# Adafruit_Rotary_Trinkey.net
KiCad netlist of a schematic drawn in EAGLE
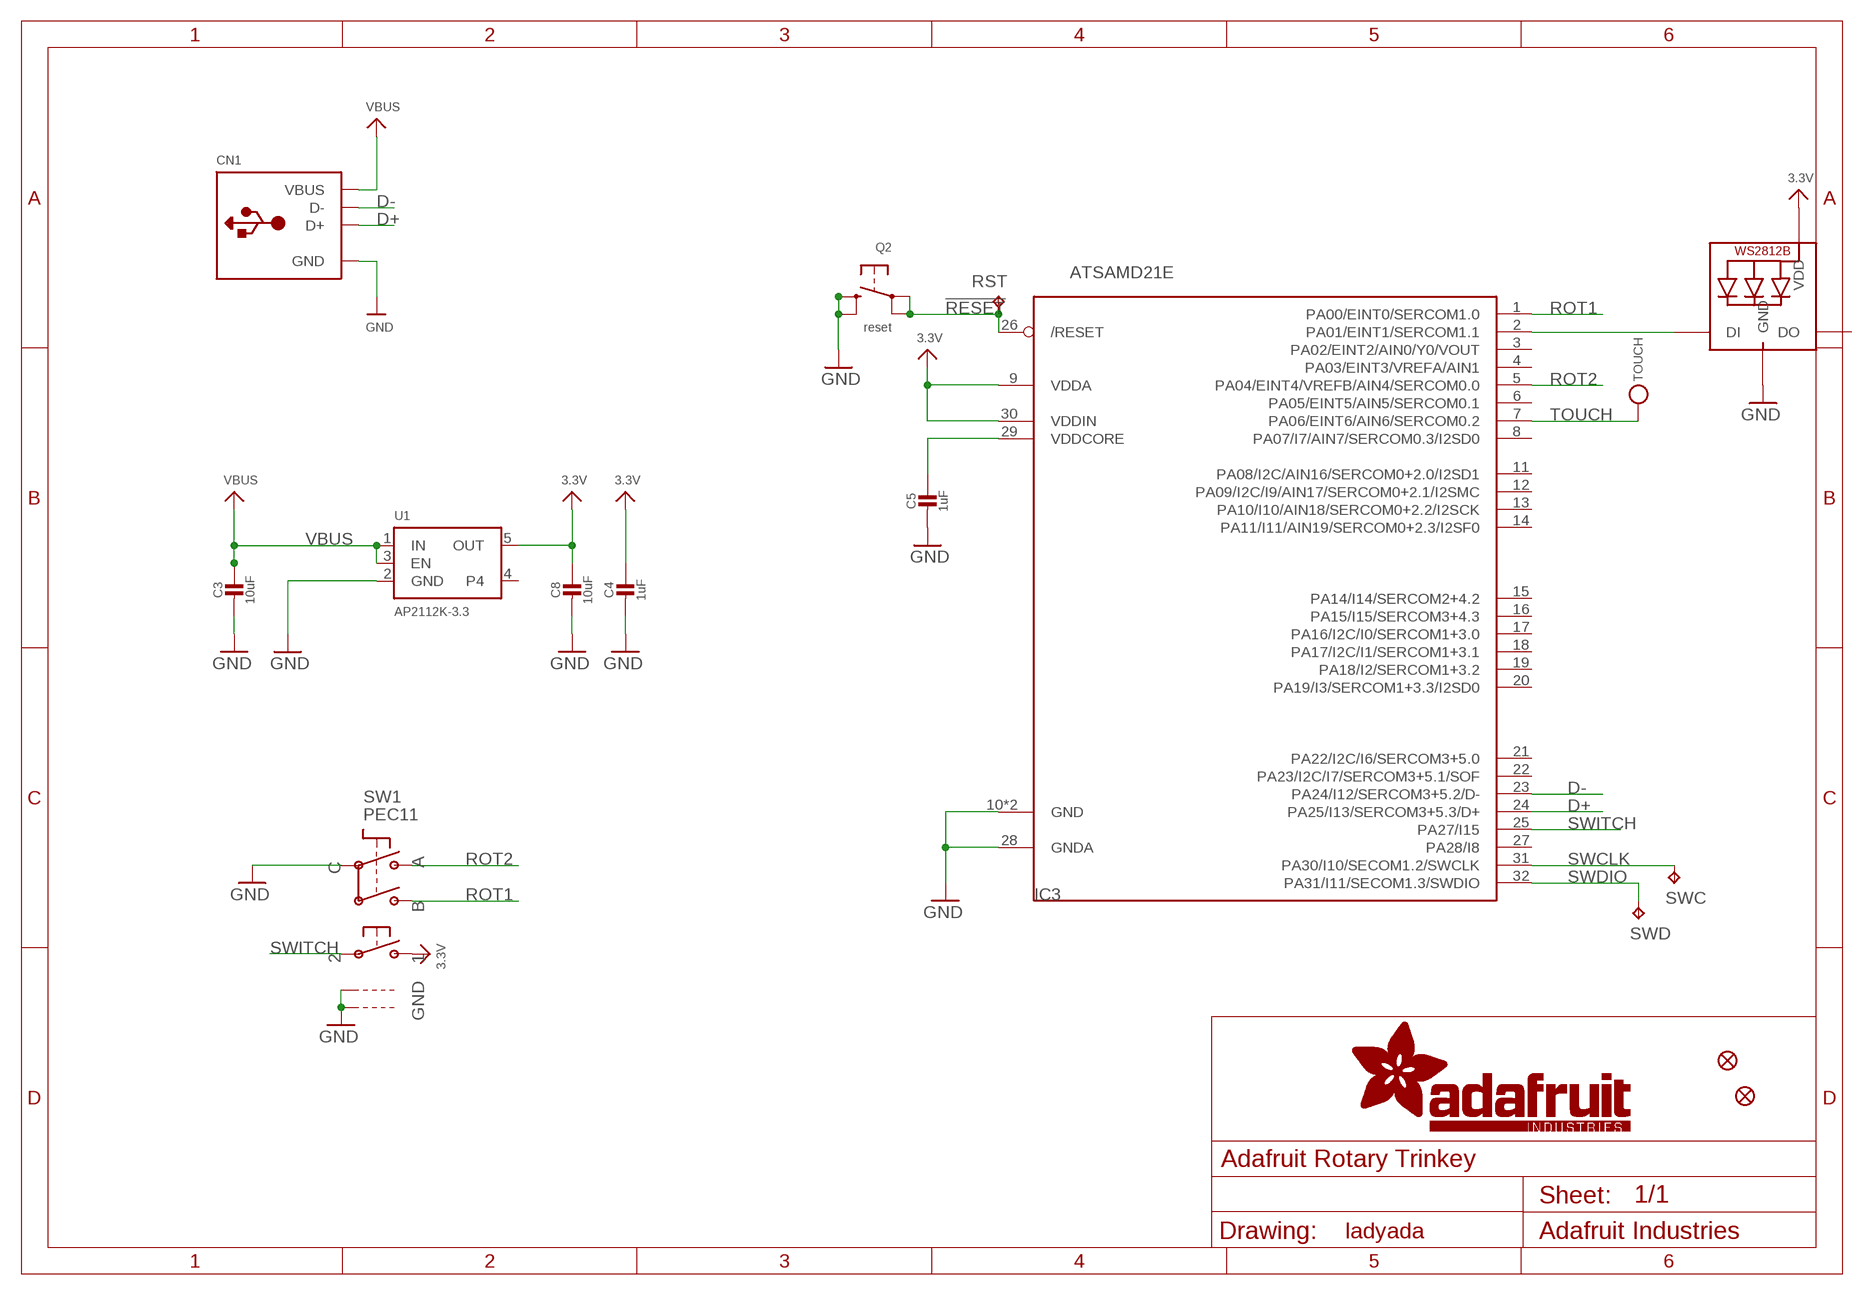
[diagram p0: schematic, sheet 1]

(export (version "E")
  (design (tool "Eeschema 10.0.6"))
  (components
    (comp (ref "C3")
      (value "10uF")
      (footprint "eagle-import:0805-NO")
      (libsource (lib "eagle-import") (part "CAP_CERAMIC0805-NOOUTLINE"))
    )
    (comp (ref "C4")
      (value "1uF")
      (footprint "eagle-import:0603-NO")
      (libsource (lib "eagle-import") (part "CAP_CERAMIC0603_NO"))
    )
    (comp (ref "C5")
      (value "1uF")
      (footprint "eagle-import:0603-NO")
      (libsource (lib "eagle-import") (part "CAP_CERAMIC0603_NO"))
    )
    (comp (ref "C8")
      (value "10uF")
      (footprint "eagle-import:0805-NO")
      (libsource (lib "eagle-import") (part "CAP_CERAMIC0805-NOOUTLINE"))
    )
    (comp (ref "CN1")
      (value "USB_TYPEAPCB")
      (footprint "eagle-import:USBA_PCB")
      (libsource (lib "eagle-import") (part "USB_TYPEAPCB"))
    )
    (comp (ref "FID1")
      (value "FIDUCIAL_1MM")
      (footprint "eagle-import:FIDUCIAL_1MM")
      (libsource (lib "eagle-import") (part "FIDUCIAL_1MM"))
    )
    (comp (ref "FID2")
      (value "FIDUCIAL_1MM")
      (footprint "eagle-import:FIDUCIAL_1MM")
      (libsource (lib "eagle-import") (part "FIDUCIAL_1MM"))
    )
    (comp (ref "IC3")
      (value "ATSAMD21E")
      (footprint "eagle-import:QFN32_5MM")
      (libsource (lib "eagle-import") (part "ATSAMD21E"))
    )
    (comp (ref "LED1")
      (value "WS2812B_SK6805_1515")
      (footprint "eagle-import:SK6805_1515")
      (libsource (lib "eagle-import") (part "WS2812B_SK6805_1515"))
    )
    (comp (ref "Q2")
      (value "reset")
      (footprint "eagle-import:BTN_KMR2_4.6X2.8")
      (libsource (lib "eagle-import") (part "SWITCH_TACT_SMT4.6X2.8"))
    )
    (comp (ref "RST")
      (value "TPTP16R")
      (footprint "eagle-import:TP16R")
      (libsource (lib "eagle-import") (part "TPTP16R"))
    )
    (comp (ref "SW1")
      (value "PEC11")
      (footprint "eagle-import:PEC11+SWITCH")
      (libsource (lib "eagle-import") (part "ENCODER_PLUS_SWITCH_PEC11_BOURNS"))
    )
    (comp (ref "SWC")
      (value "TPTP16R")
      (footprint "eagle-import:TP16R")
      (libsource (lib "eagle-import") (part "TPTP16R"))
    )
    (comp (ref "SWD")
      (value "TPTP16R")
      (footprint "eagle-import:TP16R")
      (libsource (lib "eagle-import") (part "TPTP16R"))
    )
    (comp (ref "TOUCH")
      (value "TESTPOINTPAD1MM")
      (footprint "eagle-import:TESTPOINT_PAD_1MM")
      (libsource (lib "eagle-import") (part "TESTPOINTPAD1MM"))
    )
    (comp (ref "U1")
      (value "AP2112K-3.3")
      (footprint "eagle-import:SOT23-5")
      (libsource (lib "eagle-import") (part "VREG_SOT23-5"))
    )
  )
  (nets
    (net (code "1") (name "/D+") (class "Default")
      (node (ref "CN1") (pin "USB_PLUS") (pinfunction "D+_USB_PLUS") (pintype "bidirectional"))
      (node (ref "IC3") (pin "24") (pinfunction "PA25/I13/SERCOM3+5.3/D+_24") (pintype "bidirectional"))
    )
    (net (code "2") (name "/D-") (class "Default")
      (node (ref "CN1") (pin "USB_NEG") (pinfunction "D-_USB_NEG") (pintype "bidirectional"))
      (node (ref "IC3") (pin "23") (pinfunction "PA24/I12/SERCOM3+5.2/D-_23") (pintype "bidirectional"))
    )
    (net (code "3") (name "/ROT1") (class "Default")
      (node (ref "IC3") (pin "1") (pinfunction "PA00/EINT0/SERCOM1.0_1") (pintype "bidirectional"))
      (node (ref "SW1") (pin "P$B") (pinfunction "P$B_P$B") (pintype "passive"))
    )
    (net (code "4") (name "/ROT2") (class "Default")
      (node (ref "IC3") (pin "5") (pinfunction "PA04/EINT4/VREFB/AIN4/SERCOM0.0_5") (pintype "bidirectional"))
      (node (ref "SW1") (pin "P$A") (pinfunction "P$A_P$A") (pintype "passive"))
    )
    (net (code "5") (name "/SWCLK") (class "Default")
      (node (ref "IC3") (pin "31") (pinfunction "PA30/I10/SECOM1.2/SWCLK_31") (pintype "bidirectional"))
      (node (ref "SWC") (pin "TP") (pinfunction "TP_TP") (pintype "input"))
    )
    (net (code "6") (name "/SWDIO") (class "Default")
      (node (ref "IC3") (pin "32") (pinfunction "PA31/I11/SECOM1.3/SWDIO_32") (pintype "bidirectional"))
      (node (ref "SWD") (pin "TP") (pinfunction "TP_TP") (pintype "input"))
    )
    (net (code "7") (name "/SWITCH") (class "Default")
      (node (ref "IC3") (pin "25") (pinfunction "PA27/I15_25") (pintype "bidirectional"))
      (node (ref "SW1") (pin "P$2") (pinfunction "P$2_P$2") (pintype "passive"))
    )
    (net (code "8") (name "/TOUCH") (class "Default")
      (node (ref "IC3") (pin "7") (pinfunction "PA06/EINT6/AIN6/SERCOM0.2_7") (pintype "bidirectional"))
      (node (ref "TOUCH") (pin "P$1") (pinfunction "P$1_P$1") (pintype "bidirectional"))
    )
    (net (code "9") (name "/~{RESET}") (class "Default")
      (node (ref "IC3") (pin "26") (pinfunction "/RESET_26") (pintype "bidirectional"))
      (node (ref "Q2") (pin "A") (pinfunction "P_A") (pintype "passive"))
      (node (ref "Q2") (pin "A'") (pinfunction "P1_A'") (pintype "passive"))
      (node (ref "RST") (pin "TP") (pinfunction "TP_TP") (pintype "input"))
    )
    (net (code "10") (name "3.3V") (class "Default")
      (node (ref "C4") (pin "1") (pinfunction "1_1") (pintype "passive"))
      (node (ref "C8") (pin "1") (pinfunction "1_1") (pintype "passive"))
      (node (ref "IC3") (pin "30") (pinfunction "VDDIN_30") (pintype "power_in"))
      (node (ref "IC3") (pin "9") (pinfunction "VDDA_9") (pintype "power_in"))
      (node (ref "LED1") (pin "2") (pinfunction "VDD_2") (pintype "power_in"))
      (node (ref "SW1") (pin "P$1") (pinfunction "P$1_P$1") (pintype "passive"))
      (node (ref "U1") (pin "5") (pinfunction "OUT_5") (pintype "power_in"))
    )
    (net (code "11") (name "GND") (class "Default")
      (node (ref "C3") (pin "2") (pinfunction "2_2") (pintype "passive"))
      (node (ref "C4") (pin "2") (pinfunction "2_2") (pintype "passive"))
      (node (ref "C5") (pin "2") (pinfunction "2_2") (pintype "passive"))
      (node (ref "C8") (pin "2") (pinfunction "2_2") (pintype "passive"))
      (node (ref "CN1") (pin "GND") (pinfunction "GND_GND") (pintype "power_in"))
      (node (ref "IC3") (pin "10") (pinfunction "GND_10") (pintype "power_in"))
      (node (ref "IC3") (pin "28") (pinfunction "GNDA_28") (pintype "power_in"))
      (node (ref "IC3") (pin "33") (pinfunction "GND_33") (pintype "power_in"))
      (node (ref "LED1") (pin "4") (pinfunction "GND_4") (pintype "power_in"))
      (node (ref "Q2") (pin "B") (pinfunction "S_B") (pintype "passive"))
      (node (ref "Q2") (pin "B'") (pinfunction "S1_B'") (pintype "passive"))
      (node (ref "SW1") (pin "P$C") (pinfunction "P$C_P$C") (pintype "passive"))
      (node (ref "SW1") (pin "P$GND1") (pinfunction "P$GND1_P$GND1") (pintype "passive"))
      (node (ref "SW1") (pin "P$GND2") (pinfunction "P$GND2_P$GND2") (pintype "passive"))
      (node (ref "U1") (pin "2") (pinfunction "GND_2") (pintype "power_in"))
    )
    (net (code "12") (name "Net-(IC3-PA01{slash}EINT1{slash}SERCOM1.1)") (class "Default")
      (node (ref "IC3") (pin "2") (pinfunction "PA01/EINT1/SERCOM1.1_2") (pintype "bidirectional"))
      (node (ref "LED1") (pin "1") (pinfunction "DI_1") (pintype "input"))
    )
    (net (code "13") (name "Net-(IC3-VDDCORE)") (class "Default")
      (node (ref "C5") (pin "1") (pinfunction "1_1") (pintype "passive"))
      (node (ref "IC3") (pin "29") (pinfunction "VDDCORE_29") (pintype "power_in"))
    )
    (net (code "14") (name "VBUS") (class "Default")
      (node (ref "C3") (pin "1") (pinfunction "1_1") (pintype "passive"))
      (node (ref "CN1") (pin "VCC") (pinfunction "VBUS_VCC") (pintype "power_in"))
      (node (ref "U1") (pin "1") (pinfunction "IN_1") (pintype "power_in"))
      (node (ref "U1") (pin "3") (pinfunction "EN_3") (pintype "input"))
    )
    (net (code "15") (name "unconnected-(IC3-PA02{slash}EINT2{slash}AIN0{slash}Y0{slash}VOUT-Pad3)") (class "Default")
      (node (ref "IC3") (pin "3") (pinfunction "PA02/EINT2/AIN0/Y0/VOUT_3") (pintype "bidirectional"))
    )
    (net (code "16") (name "unconnected-(IC3-PA03{slash}EINT3{slash}VREFA{slash}AIN1-Pad4)") (class "Default")
      (node (ref "IC3") (pin "4") (pinfunction "PA03/EINT3/VREFA/AIN1_4") (pintype "bidirectional"))
    )
    (net (code "17") (name "unconnected-(IC3-PA05{slash}EINT5{slash}AIN5{slash}SERCOM0.1-Pad6)") (class "Default")
      (node (ref "IC3") (pin "6") (pinfunction "PA05/EINT5/AIN5/SERCOM0.1_6") (pintype "bidirectional"))
    )
    (net (code "18") (name "unconnected-(IC3-PA07{slash}I7{slash}AIN7{slash}SERCOM0.3{slash}I2SD0-Pad8)") (class "Default")
      (node (ref "IC3") (pin "8") (pinfunction "PA07/I7/AIN7/SERCOM0.3/I2SD0_8") (pintype "bidirectional"))
    )
    (net (code "19") (name "unconnected-(IC3-PA08{slash}I2C{slash}AIN16{slash}SERCOM0+2.0{slash}I2SD1-Pad11)") (class "Default")
      (node (ref "IC3") (pin "11") (pinfunction "PA08/I2C/AIN16/SERCOM0+2.0/I2SD1_11") (pintype "bidirectional"))
    )
    (net (code "20") (name "unconnected-(IC3-PA09{slash}I2C{slash}I9{slash}AIN17{slash}SERCOM0+2.1{slash}I2SMC-Pad12)") (class "Default")
      (node (ref "IC3") (pin "12") (pinfunction "PA09/I2C/I9/AIN17/SERCOM0+2.1/I2SMC_12") (pintype "bidirectional"))
    )
    (net (code "21") (name "unconnected-(IC3-PA10{slash}I10{slash}AIN18{slash}SERCOM0+2.2{slash}I2SCK-Pad13)") (class "Default")
      (node (ref "IC3") (pin "13") (pinfunction "PA10/I10/AIN18/SERCOM0+2.2/I2SCK_13") (pintype "bidirectional"))
    )
    (net (code "22") (name "unconnected-(IC3-PA11{slash}I11{slash}AIN19{slash}SERCOM0+2.3{slash}I2SF0-Pad14)") (class "Default")
      (node (ref "IC3") (pin "14") (pinfunction "PA11/I11/AIN19/SERCOM0+2.3/I2SF0_14") (pintype "bidirectional"))
    )
    (net (code "23") (name "unconnected-(IC3-PA14{slash}I14{slash}SERCOM2+4.2-Pad15)") (class "Default")
      (node (ref "IC3") (pin "15") (pinfunction "PA14/I14/SERCOM2+4.2_15") (pintype "bidirectional"))
    )
    (net (code "24") (name "unconnected-(IC3-PA15{slash}I15{slash}SERCOM3+4.3-Pad16)") (class "Default")
      (node (ref "IC3") (pin "16") (pinfunction "PA15/I15/SERCOM3+4.3_16") (pintype "bidirectional"))
    )
    (net (code "25") (name "unconnected-(IC3-PA16{slash}I2C{slash}I0{slash}SERCOM1+3.0-Pad17)") (class "Default")
      (node (ref "IC3") (pin "17") (pinfunction "PA16/I2C/I0/SERCOM1+3.0_17") (pintype "bidirectional"))
    )
    (net (code "26") (name "unconnected-(IC3-PA17{slash}I2C{slash}I1{slash}SERCOM1+3.1-Pad18)") (class "Default")
      (node (ref "IC3") (pin "18") (pinfunction "PA17/I2C/I1/SERCOM1+3.1_18") (pintype "bidirectional"))
    )
    (net (code "27") (name "unconnected-(IC3-PA18{slash}I2{slash}SERCOM1+3.2-Pad19)") (class "Default")
      (node (ref "IC3") (pin "19") (pinfunction "PA18/I2/SERCOM1+3.2_19") (pintype "bidirectional"))
    )
    (net (code "28") (name "unconnected-(IC3-PA19{slash}I3{slash}SERCOM1+3.3{slash}I2SD0-Pad20)") (class "Default")
      (node (ref "IC3") (pin "20") (pinfunction "PA19/I3/SERCOM1+3.3/I2SD0_20") (pintype "bidirectional"))
    )
    (net (code "29") (name "unconnected-(IC3-PA22{slash}I2C{slash}I6{slash}SERCOM3+5.0-Pad21)") (class "Default")
      (node (ref "IC3") (pin "21") (pinfunction "PA22/I2C/I6/SERCOM3+5.0_21") (pintype "bidirectional"))
    )
    (net (code "30") (name "unconnected-(IC3-PA23{slash}I2C{slash}I7{slash}SERCOM3+5.1{slash}SOF-Pad22)") (class "Default")
      (node (ref "IC3") (pin "22") (pinfunction "PA23/I2C/I7/SERCOM3+5.1/SOF_22") (pintype "bidirectional"))
    )
    (net (code "31") (name "unconnected-(IC3-PA28{slash}I8-Pad27)") (class "Default")
      (node (ref "IC3") (pin "27") (pinfunction "PA28/I8_27") (pintype "bidirectional"))
    )
    (net (code "32") (name "unconnected-(LED1-DO-Pad3)") (class "Default")
      (node (ref "LED1") (pin "3") (pinfunction "DO_3") (pintype "output"))
    )
    (net (code "33") (name "unconnected-(U1-P4-Pad4)") (class "Default")
      (node (ref "U1") (pin "4") (pinfunction "P4_4") (pintype "bidirectional"))
    )
  )
)
